# Delibird_PIL.net
KiCad netlist of a schematic drawn in Altium Designer
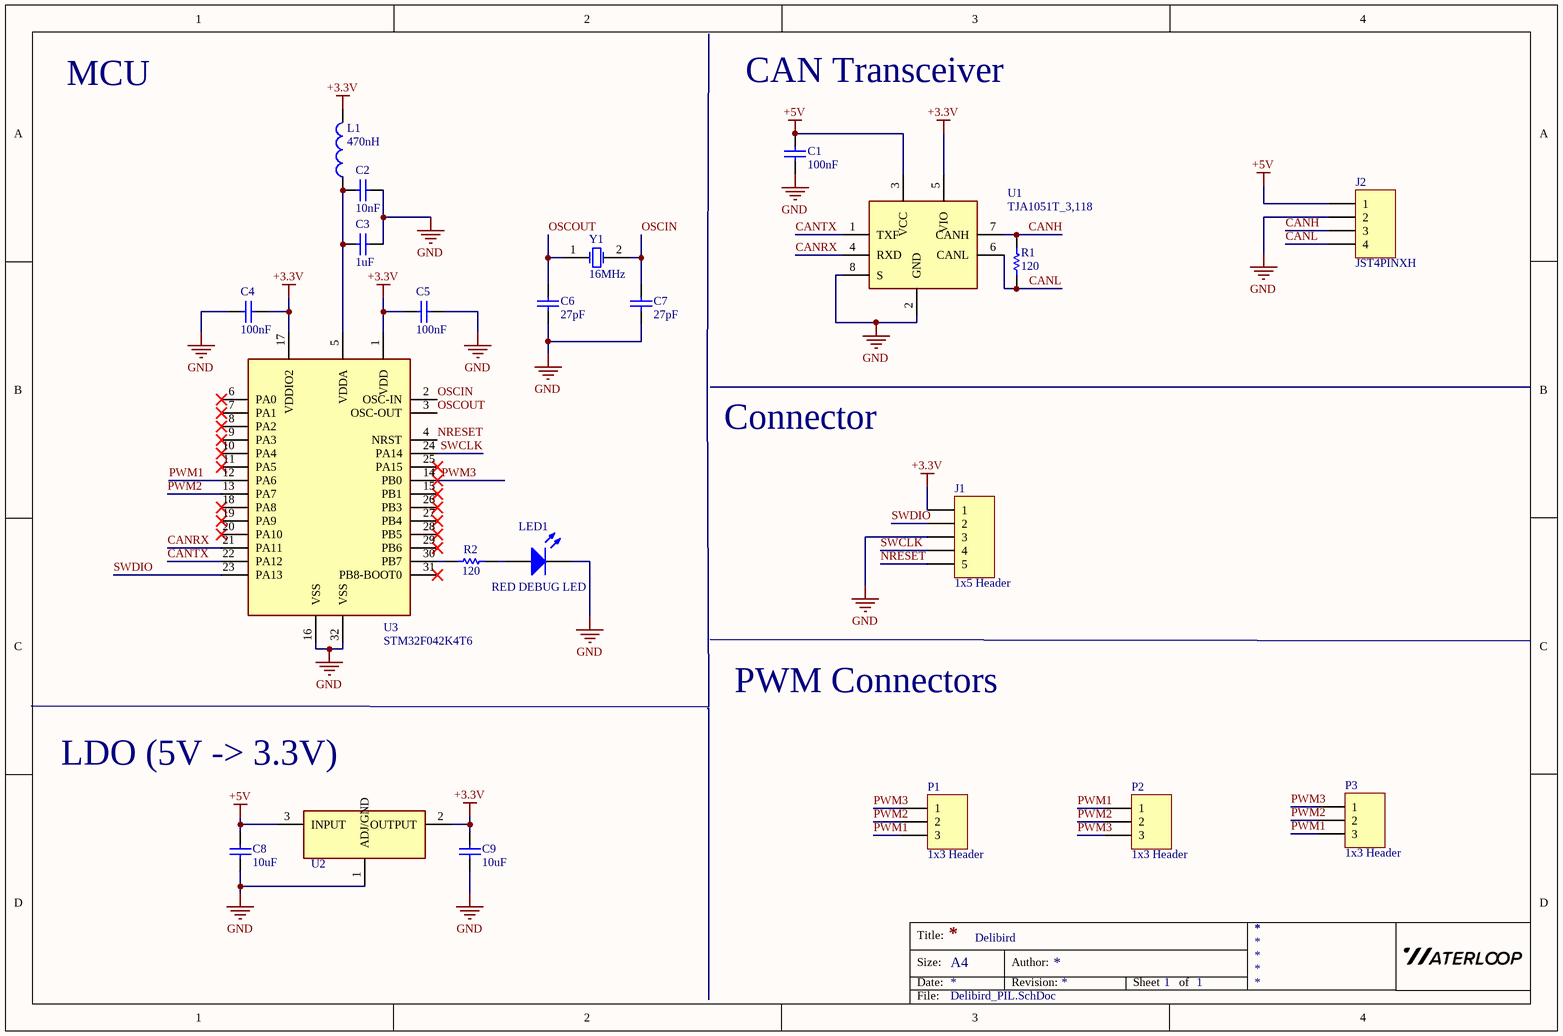
[diagram p0: Delibird_PIL.SchDoc]

(export (version "E")
  (design (tool "Eeschema 10.0.6"))
  (components
    (comp (ref "C1")
      (value "100nF")
      (footprint "0805 - Capacitor")
      (description "Nonpolarized Capacitor")
      (fields (field (name "Comment") "Capacitor - Nonpolarized"))
      (libsource (lib "General") (part "Capacitor - Nonpolarized"))
    )
    (comp (ref "C2")
      (value "10nF")
      (footprint "0805 - Capacitor")
      (description "Nonpolarized Capacitor")
      (fields (field (name "Comment") "Capacitor - Nonpolarized"))
      (libsource (lib "General") (part "Capacitor - Nonpolarized"))
    )
    (comp (ref "C3")
      (value "1uF")
      (footprint "0805 - Capacitor")
      (description "Nonpolarized Capacitor")
      (fields (field (name "Comment") "Capacitor - Nonpolarized"))
      (libsource (lib "General") (part "Capacitor - Nonpolarized"))
    )
    (comp (ref "C4")
      (value "100nF")
      (footprint "0805 - Capacitor")
      (description "Nonpolarized Capacitor")
      (fields (field (name "Comment") "Capacitor - Nonpolarized"))
      (libsource (lib "General") (part "Capacitor - Nonpolarized"))
    )
    (comp (ref "C5")
      (value "100nF")
      (footprint "0805 - Capacitor")
      (description "Nonpolarized Capacitor")
      (fields (field (name "Comment") "Capacitor - Nonpolarized"))
      (libsource (lib "General") (part "Capacitor - Nonpolarized"))
    )
    (comp (ref "C6")
      (value "27pF")
      (footprint "0805 - Capacitor")
      (description "Nonpolarized Capacitor")
      (fields (field (name "Comment") "Capacitor - Nonpolarized"))
      (libsource (lib "General") (part "Capacitor - Nonpolarized"))
    )
    (comp (ref "C7")
      (value "27pF")
      (footprint "0805 - Capacitor")
      (description "Nonpolarized Capacitor")
      (fields (field (name "Comment") "Capacitor - Nonpolarized"))
      (libsource (lib "General") (part "Capacitor - Nonpolarized"))
    )
    (comp (ref "C8")
      (value "10uF")
      (footprint "0805 - Capacitor")
      (description "Nonpolarized Capacitor")
      (fields (field (name "Comment") "Capacitor - Nonpolarized"))
      (libsource (lib "General") (part "Capacitor - Nonpolarized"))
    )
    (comp (ref "C9")
      (value "10uF")
      (footprint "0805 - Capacitor")
      (description "Nonpolarized Capacitor")
      (fields (field (name "Comment") "Capacitor - Nonpolarized"))
      (libsource (lib "General") (part "Capacitor - Nonpolarized"))
    )
    (comp (ref "J1")
      (value "1x5 Header")
      (footprint "HDR1X5")
      (description "1x5 Pin Header")
      (libsource (lib "GeneralConnectors") (part "1x5 Header"))
    )
    (comp (ref "J2")
      (value "JST4PINXH")
      (footprint "B4B-XH")
      (description "1x4 Pin Header")
      (libsource (lib "GeneralConnectors") (part "1x4 Header"))
    )
    (comp (ref "L1")
      (value "470nH")
      (footprint "0805 - Capacitor")
      (description "Inductor")
      (libsource (lib "General") (part "Inductor"))
    )
    (comp (ref "LED1")
      (value "RED DEBUG LED")
      (footprint "0805 - Resistor")
      (description "Light Emitting Diode")
      (libsource (lib "General") (part "LED"))
    )
    (comp (ref "P1")
      (value "1x3 Header")
      (footprint "B3B-XH")
      (description "1x3 Pin Header")
      (libsource (lib "GeneralConnectors") (part "1x3 Header"))
    )
    (comp (ref "P2")
      (value "1x3 Header")
      (footprint "B3B-XH")
      (description "1x3 Pin Header")
      (libsource (lib "GeneralConnectors") (part "1x3 Header"))
    )
    (comp (ref "P3")
      (value "1x3 Header")
      (footprint "B3B-XH")
      (description "1x3 Pin Header")
      (libsource (lib "GeneralConnectors") (part "1x3 Header"))
    )
    (comp (ref "R1")
      (value "120")
      (footprint "0603 - Resistor")
      (description "Resistor")
      (libsource (lib "General") (part "Resistor"))
    )
    (comp (ref "R2")
      (value "120")
      (footprint "0603 - Resistor")
      (description "Resistor")
      (libsource (lib "General") (part "Resistor"))
    )
    (comp (ref "U1")
      (value "TJA1051T_3,118")
      (footprint "TJA1051T/3,118")
      (description "CAN Transceiver IC 4.5V-5.5V 250ns")
      (fields (field (name "MANUFACTURER") "NXP") (field (name "MANUFACTURER PART NUMBER") "TJA1051T/3,118"))
      (libsource (lib "GeneralComponents") (part "TJA1051T_3,118"))
    )
    (comp (ref "U2")
      (value "TLV1117-33IDCYR")
      (footprint "TLV1117")
      (description "Linear Voltage Regulator IC 3.3V 800MA SOT223-4")
      (fields (field (name "MANUFACTURER") "Texas Instruments"))
      (libsource (lib "GeneralComponents") (part "TLV1117-33IDCYR"))
    )
    (comp (ref "U3")
      (value "STM32F042K4T6")
      (footprint "QFP80P900X900X160-32N")
      (description "Microcontroller")
      (fields (field (name "MOUSER PART NUMBER") "511-STM32F042K4T6"))
      (libsource (lib "Embedded") (part "STM32F042K4T6"))
    )
    (comp (ref "Y1")
      (value "16MHz")
      (footprint "2-SMD NO LEAD CRSYSTAL")
      (description "Crystal Oscillator")
      (fields (field (name "Comment") "Oscillator"))
      (libsource (lib "General") (part "Oscillator"))
    )
  )
  (nets
    (net (code "1") (name "+3.3V") (class "Default")
      (node (ref "C4") (pin "1") (pinfunction "1_1") (pintype "passive"))
      (node (ref "C5") (pin "2") (pinfunction "2_2") (pintype "passive"))
      (node (ref "C9") (pin "2") (pinfunction "2_2") (pintype "passive"))
      (node (ref "J1") (pin "1") (pinfunction "1_1") (pintype "passive"))
      (node (ref "L1") (pin "2") (pinfunction "2_2") (pintype "passive"))
      (node (ref "U1") (pin "5") (pinfunction "VIO_5") (pintype "passive"))
      (node (ref "U2") (pin "2") (pinfunction "OUTPUT_2") (pintype "passive"))
      (node (ref "U3") (pin "1") (pinfunction "VDD_1") (pintype "passive"))
      (node (ref "U3") (pin "17") (pinfunction "VDDIO2_17") (pintype "passive"))
    )
    (net (code "2") (name "+5V") (class "Default")
      (node (ref "C1") (pin "2") (pinfunction "2_2") (pintype "passive"))
      (node (ref "C8") (pin "1") (pinfunction "1_1") (pintype "passive"))
      (node (ref "J2") (pin "1") (pinfunction "1_1") (pintype "passive"))
      (node (ref "U1") (pin "3") (pinfunction "VCC_3") (pintype "passive"))
      (node (ref "U2") (pin "3") (pinfunction "INPUT_3") (pintype "passive"))
    )
    (net (code "3") (name "/CANH") (class "Default")
      (node (ref "J2") (pin "3") (pinfunction "3_3") (pintype "passive"))
      (node (ref "R1") (pin "2") (pinfunction "2_2") (pintype "passive"))
      (node (ref "U1") (pin "7") (pinfunction "CANH_7") (pintype "passive"))
    )
    (net (code "4") (name "/CANL") (class "Default")
      (node (ref "J2") (pin "4") (pinfunction "4_4") (pintype "passive"))
      (node (ref "R1") (pin "1") (pinfunction "1_1") (pintype "passive"))
      (node (ref "U1") (pin "6") (pinfunction "CANL_6") (pintype "passive"))
    )
    (net (code "5") (name "/CANRX") (class "Default")
      (node (ref "U1") (pin "4") (pinfunction "RXD_4") (pintype "passive"))
      (node (ref "U3") (pin "21") (pinfunction "PA11_21") (pintype "passive"))
    )
    (net (code "6") (name "/CANTX") (class "Default")
      (node (ref "U1") (pin "1") (pinfunction "TXF_1") (pintype "passive"))
      (node (ref "U3") (pin "22") (pinfunction "PA12_22") (pintype "passive"))
    )
    (net (code "7") (name "/NRESET") (class "Default")
      (node (ref "J1") (pin "5") (pinfunction "5_5") (pintype "passive"))
      (node (ref "U3") (pin "4") (pinfunction "NRST_4") (pintype "passive"))
    )
    (net (code "8") (name "/OSCIN") (class "Default")
      (node (ref "C7") (pin "2") (pinfunction "2_2") (pintype "passive"))
      (node (ref "U3") (pin "2") (pinfunction "OSC-IN_2") (pintype "passive"))
      (node (ref "Y1") (pin "2") (pinfunction "OSC2_2") (pintype "passive"))
    )
    (net (code "9") (name "/OSCOUT") (class "Default")
      (node (ref "C6") (pin "2") (pinfunction "2_2") (pintype "passive"))
      (node (ref "U3") (pin "3") (pinfunction "OSC-OUT_3") (pintype "passive"))
      (node (ref "Y1") (pin "1") (pinfunction "OSC1_1") (pintype "passive"))
    )
    (net (code "10") (name "/PWM1") (class "Default")
      (node (ref "P1") (pin "3") (pinfunction "3_3") (pintype "passive"))
      (node (ref "P2") (pin "1") (pinfunction "1_1") (pintype "passive"))
      (node (ref "P3") (pin "3") (pinfunction "3_3") (pintype "passive"))
      (node (ref "U3") (pin "12") (pinfunction "PA6_12") (pintype "passive"))
    )
    (net (code "11") (name "/PWM2") (class "Default")
      (node (ref "P1") (pin "2") (pinfunction "2_2") (pintype "passive"))
      (node (ref "P2") (pin "2") (pinfunction "2_2") (pintype "passive"))
      (node (ref "P3") (pin "2") (pinfunction "2_2") (pintype "passive"))
      (node (ref "U3") (pin "13") (pinfunction "PA7_13") (pintype "passive"))
    )
    (net (code "12") (name "/PWM3") (class "Default")
      (node (ref "P1") (pin "1") (pinfunction "1_1") (pintype "passive"))
      (node (ref "P2") (pin "3") (pinfunction "3_3") (pintype "passive"))
      (node (ref "P3") (pin "1") (pinfunction "1_1") (pintype "passive"))
      (node (ref "U3") (pin "14") (pinfunction "PB0_14") (pintype "passive"))
    )
    (net (code "13") (name "/SWCLK") (class "Default")
      (node (ref "J1") (pin "4") (pinfunction "4_4") (pintype "passive"))
      (node (ref "U3") (pin "24") (pinfunction "PA14_24") (pintype "passive"))
    )
    (net (code "14") (name "/SWDIO") (class "Default")
      (node (ref "J1") (pin "2") (pinfunction "2_2") (pintype "passive"))
      (node (ref "U3") (pin "23") (pinfunction "PA13_23") (pintype "passive"))
    )
    (net (code "15") (name "GND") (class "Default")
      (node (ref "C1") (pin "1") (pinfunction "1_1") (pintype "passive"))
      (node (ref "C2") (pin "2") (pinfunction "2_2") (pintype "passive"))
      (node (ref "C3") (pin "2") (pinfunction "2_2") (pintype "passive"))
      (node (ref "C4") (pin "2") (pinfunction "2_2") (pintype "passive"))
      (node (ref "C5") (pin "1") (pinfunction "1_1") (pintype "passive"))
      (node (ref "C6") (pin "1") (pinfunction "1_1") (pintype "passive"))
      (node (ref "C7") (pin "1") (pinfunction "1_1") (pintype "passive"))
      (node (ref "C8") (pin "2") (pinfunction "2_2") (pintype "passive"))
      (node (ref "C9") (pin "1") (pinfunction "1_1") (pintype "passive"))
      (node (ref "J1") (pin "3") (pinfunction "3_3") (pintype "passive"))
      (node (ref "J2") (pin "2") (pinfunction "2_2") (pintype "passive"))
      (node (ref "LED1") (pin "2") (pinfunction "K_2") (pintype "passive"))
      (node (ref "U1") (pin "2") (pinfunction "GND_2") (pintype "passive"))
      (node (ref "U1") (pin "8") (pinfunction "S_8") (pintype "passive"))
      (node (ref "U2") (pin "1") (pinfunction "ADJ/GND_1") (pintype "passive"))
      (node (ref "U3") (pin "16") (pinfunction "VSS_16") (pintype "passive"))
      (node (ref "U3") (pin "32") (pinfunction "VSS_32") (pintype "passive"))
    )
    (net (code "16") (name "Net-(LED1-A)") (class "Default")
      (node (ref "LED1") (pin "1") (pinfunction "A_1") (pintype "passive"))
      (node (ref "R2") (pin "2") (pinfunction "2_2") (pintype "passive"))
    )
    (net (code "17") (name "Net-(U3-PB7)") (class "Default")
      (node (ref "R2") (pin "1") (pinfunction "1_1") (pintype "passive"))
      (node (ref "U3") (pin "30") (pinfunction "PB7_30") (pintype "passive"))
    )
    (net (code "18") (name "Net-(U3-VDDA)") (class "Default")
      (node (ref "C2") (pin "1") (pinfunction "1_1") (pintype "passive"))
      (node (ref "C3") (pin "1") (pinfunction "1_1") (pintype "passive"))
      (node (ref "L1") (pin "1") (pinfunction "1_1") (pintype "passive"))
      (node (ref "U3") (pin "5") (pinfunction "VDDA_5") (pintype "passive"))
    )
    (net (code "19") (name "unconnected-(U3-PA0-Pad6)") (class "Default")
      (node (ref "U3") (pin "6") (pinfunction "PA0_6") (pintype "passive+no_connect"))
    )
    (net (code "20") (name "unconnected-(U3-PA1-Pad7)") (class "Default")
      (node (ref "U3") (pin "7") (pinfunction "PA1_7") (pintype "passive+no_connect"))
    )
    (net (code "21") (name "unconnected-(U3-PA2-Pad8)") (class "Default")
      (node (ref "U3") (pin "8") (pinfunction "PA2_8") (pintype "passive+no_connect"))
    )
    (net (code "22") (name "unconnected-(U3-PA3-Pad9)") (class "Default")
      (node (ref "U3") (pin "9") (pinfunction "PA3_9") (pintype "passive+no_connect"))
    )
    (net (code "23") (name "unconnected-(U3-PA4-Pad10)") (class "Default")
      (node (ref "U3") (pin "10") (pinfunction "PA4_10") (pintype "passive+no_connect"))
    )
    (net (code "24") (name "unconnected-(U3-PA5-Pad11)") (class "Default")
      (node (ref "U3") (pin "11") (pinfunction "PA5_11") (pintype "passive+no_connect"))
    )
    (net (code "25") (name "unconnected-(U3-PA8-Pad18)") (class "Default")
      (node (ref "U3") (pin "18") (pinfunction "PA8_18") (pintype "passive+no_connect"))
    )
    (net (code "26") (name "unconnected-(U3-PA9-Pad19)") (class "Default")
      (node (ref "U3") (pin "19") (pinfunction "PA9_19") (pintype "passive+no_connect"))
    )
    (net (code "27") (name "unconnected-(U3-PA10-Pad20)") (class "Default")
      (node (ref "U3") (pin "20") (pinfunction "PA10_20") (pintype "passive+no_connect"))
    )
    (net (code "28") (name "unconnected-(U3-PA15-Pad25)") (class "Default")
      (node (ref "U3") (pin "25") (pinfunction "PA15_25") (pintype "passive+no_connect"))
    )
    (net (code "29") (name "unconnected-(U3-PB1-Pad15)") (class "Default")
      (node (ref "U3") (pin "15") (pinfunction "PB1_15") (pintype "passive+no_connect"))
    )
    (net (code "30") (name "unconnected-(U3-PB3-Pad26)") (class "Default")
      (node (ref "U3") (pin "26") (pinfunction "PB3_26") (pintype "passive+no_connect"))
    )
    (net (code "31") (name "unconnected-(U3-PB4-Pad27)") (class "Default")
      (node (ref "U3") (pin "27") (pinfunction "PB4_27") (pintype "passive+no_connect"))
    )
    (net (code "32") (name "unconnected-(U3-PB5-Pad28)") (class "Default")
      (node (ref "U3") (pin "28") (pinfunction "PB5_28") (pintype "passive+no_connect"))
    )
    (net (code "33") (name "unconnected-(U3-PB6-Pad29)") (class "Default")
      (node (ref "U3") (pin "29") (pinfunction "PB6_29") (pintype "passive+no_connect"))
    )
    (net (code "34") (name "unconnected-(U3-PB8-BOOT0-Pad31)") (class "Default")
      (node (ref "U3") (pin "31") (pinfunction "PB8-BOOT0_31") (pintype "passive+no_connect"))
    )
  )
)
